# MIDI.net
KiCad netlist of a schematic drawn in Altium Designer
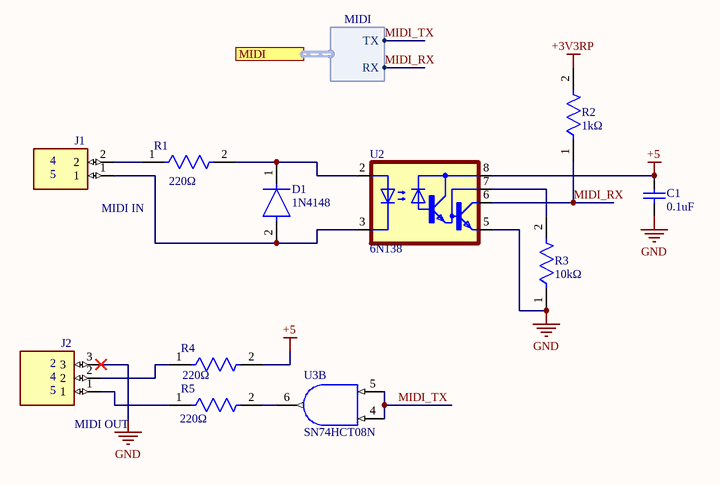
[diagram p0: MIDI.SchDoc]

(export (version "E")
  (design (tool "Eeschema 10.0.6"))
  (components
    (comp (ref "C1")
      (value "0.1uF")
      (footprint "CAPR51-254-508X318X736")
      (libsource (lib "Components - 05.08.25 - 01.44") (part "CMP-1664-00004-1"))
    )
    (comp (ref "D1")
      (value "1N4148")
      (footprint "FP-017AG-MFG")
      (description "DIODE GEN PURP 100V 200MA DO35")
      (fields (field (name "VOLTAGE") "100V"))
      (libsource (lib "Components - 05.08.25 - 13.30") (part "CMP-07163-000046-1"))
    )
    (comp (ref "J1")
      (value "MIDI IN")
      (footprint "SHDR2W100P0X500_1X2_1000X760X1")
      (description "2 Position Wire to Board Terminal Block Horizontal with Board 0.197 (5.00mm) Through Hole")
      (fields (field (name "MF") "Molex") (field (name "MP") "395430602"))
      (libsource (lib "39543-0602") (part "39543-0602"))
    )
    (comp (ref "J2")
      (value "MIDI OUT")
      (footprint "39543-0603")
      (description "3 Position Wire to Board Terminal Block Horizontal with Board 0.197 (5.00mm) Through Hole")
      (fields (field (name "MF") "Molex") (field (name "MP") "395430603"))
      (libsource (lib "39543-0603") (part "39543-0603"))
    )
    (comp (ref "R1")
      (value "CMF5073K200FHEB")
      (footprint "FP-CMF50-0")
      (description "CMF5073K200FHEB Res Metal Film 73.2K Ohm 1% 0.125W(1/8W) ±50ppm/°C Epoxy AXL T/R")
      (fields (field (name "TOLERANCE") "1%") (field (name "RESISTANCE") "220Ω"))
      (libsource (lib "Altium Content Vault") (part "1029c3af85768c4190bb7ad29bc67b5"))
    )
    (comp (ref "R2")
      (value "CMF5073K200FHEB")
      (footprint "FP-CMF50-0")
      (description "CMF5073K200FHEB Res Metal Film 73.2K Ohm 1% 0.125W(1/8W) ±50ppm/°C Epoxy AXL T/R")
      (fields (field (name "TOLERANCE") "1%") (field (name "RESISTANCE") "1kΩ"))
      (libsource (lib "Altium Content Vault") (part "1029c3af85768c4190bb7ad29bc67b5"))
    )
    (comp (ref "R3")
      (value "CMF5073K200FHEB")
      (footprint "FP-CMF50-0")
      (description "CMF5073K200FHEB Res Metal Film 73.2K Ohm 1% 0.125W(1/8W) ±50ppm/°C Epoxy AXL T/R")
      (fields (field (name "TOLERANCE") "1%") (field (name "RESISTANCE") "10kΩ"))
      (libsource (lib "Altium Content Vault") (part "1029c3af85768c4190bb7ad29bc67b5"))
    )
    (comp (ref "R4")
      (value "CMF5073K200FHEB")
      (footprint "FP-CMF50-0")
      (description "CMF5073K200FHEB Res Metal Film 73.2K Ohm 1% 0.125W(1/8W) ±50ppm/°C Epoxy AXL T/R")
      (fields (field (name "TOLERANCE") "1%") (field (name "RESISTANCE") "220Ω"))
      (libsource (lib "Altium Content Vault") (part "1029c3af85768c4190bb7ad29bc67b5"))
    )
    (comp (ref "R5")
      (value "CMF5073K200FHEB")
      (footprint "FP-CMF50-0")
      (description "CMF5073K200FHEB Res Metal Film 73.2K Ohm 1% 0.125W(1/8W) ±50ppm/°C Epoxy AXL T/R")
      (fields (field (name "TOLERANCE") "1%") (field (name "RESISTANCE") "220Ω"))
      (libsource (lib "Altium Content Vault") (part "1029c3af85768c4190bb7ad29bc67b5"))
    )
    (comp (ref "U2")
      (value "6N138")
      (footprint "DIP762W50P254L1018H450Q8")
      (fields (field (name "MF") "Isocom Components"))
      (libsource (lib "6N138") (part "6N138"))
    )
    (comp (ref "U3")
      (value "SN74HCT08N")
      (footprint "N0014A")
      (description "Quadruple 2-Input Positive-AND Gates, N0014A, TUBE")
      (fields
        (field (name "MANUFACTURER") "Texas Instruments")
        (field (name "GENERIC PART NUMBER") "SN74HCT08")
      )
      (libsource (lib "Components - 05.08.25 - 14.49") (part "CMP-0777-00257-3"))
    )
  )
  (nets
    (net (code "2") (name "+3V3RP") (class "Default")
      (node (ref "R2") (pin "2") (pinfunction "2_2") (pintype "passive"))
    )
    (net (code "3") (name "+5") (class "Default")
      (node (ref "C1") (pin "2") (pinfunction "2_2") (pintype "passive"))
      (node (ref "R4") (pin "2") (pinfunction "2_2") (pintype "passive"))
      (node (ref "U2") (pin "8") (pinfunction "VCC_8") (pintype "passive"))
    )
    (net (code "4") (name "/MIDI_RX") (class "Default")
      (node (ref "R2") (pin "1") (pinfunction "1_1") (pintype "passive"))
      (node (ref "U2") (pin "6") (pinfunction "VO_6") (pintype "passive"))
    )
    (net (code "5") (name "/MIDI_TX") (class "Default")
      (node (ref "U3") (pin "4") (pinfunction "2A_4") (pintype "input"))
      (node (ref "U3") (pin "5") (pinfunction "2B_5") (pintype "input"))
    )
    (net (code "7") (name "GND") (class "Default")
      (node (ref "C1") (pin "1") (pinfunction "1_1") (pintype "passive"))
      (node (ref "J2") (pin "3") (pinfunction "3_3") (pintype "bidirectional"))
      (node (ref "R3") (pin "1") (pinfunction "1_1") (pintype "passive"))
      (node (ref "U2") (pin "5") (pinfunction "GND_5") (pintype "passive"))
    )
    (net (code "8") (name "Net-(D1-A)") (class "Default")
      (node (ref "D1") (pin "2") (pinfunction "A_2") (pintype "passive"))
      (node (ref "J1") (pin "1") (pinfunction "1_1") (pintype "bidirectional"))
      (node (ref "U2") (pin "3") (pinfunction "C_3") (pintype "passive"))
    )
    (net (code "9") (name "Net-(D1-C)") (class "Default")
      (node (ref "D1") (pin "1") (pinfunction "C_1") (pintype "passive"))
      (node (ref "R1") (pin "2") (pinfunction "2_2") (pintype "passive"))
      (node (ref "U2") (pin "2") (pinfunction "A_2") (pintype "passive"))
    )
    (net (code "10") (name "Net-(J1-Pad2)") (class "Default")
      (node (ref "J1") (pin "2") (pinfunction "2_2") (pintype "bidirectional"))
      (node (ref "R1") (pin "1") (pinfunction "1_1") (pintype "passive"))
    )
    (net (code "11") (name "Net-(J2-Pad1)") (class "Default")
      (node (ref "J2") (pin "1") (pinfunction "1_1") (pintype "bidirectional"))
      (node (ref "R5") (pin "1") (pinfunction "1_1") (pintype "passive"))
    )
    (net (code "12") (name "Net-(J2-Pad2)") (class "Default")
      (node (ref "J2") (pin "2") (pinfunction "2_2") (pintype "bidirectional"))
      (node (ref "R4") (pin "1") (pinfunction "1_1") (pintype "passive"))
    )
    (net (code "13") (name "Net-(U2-VB)") (class "Default")
      (node (ref "R3") (pin "2") (pinfunction "2_2") (pintype "passive"))
      (node (ref "U2") (pin "7") (pinfunction "VB_7") (pintype "passive"))
    )
    (net (code "14") (name "Net-(U3B-2Y)") (class "Default")
      (node (ref "R5") (pin "2") (pinfunction "2_2") (pintype "passive"))
      (node (ref "U3") (pin "6") (pinfunction "2Y_6") (pintype "output"))
    )
  )
)
